# Serial-Basic-CH340E-and-USBC.net
KiCad netlist of a schematic drawn in EAGLE
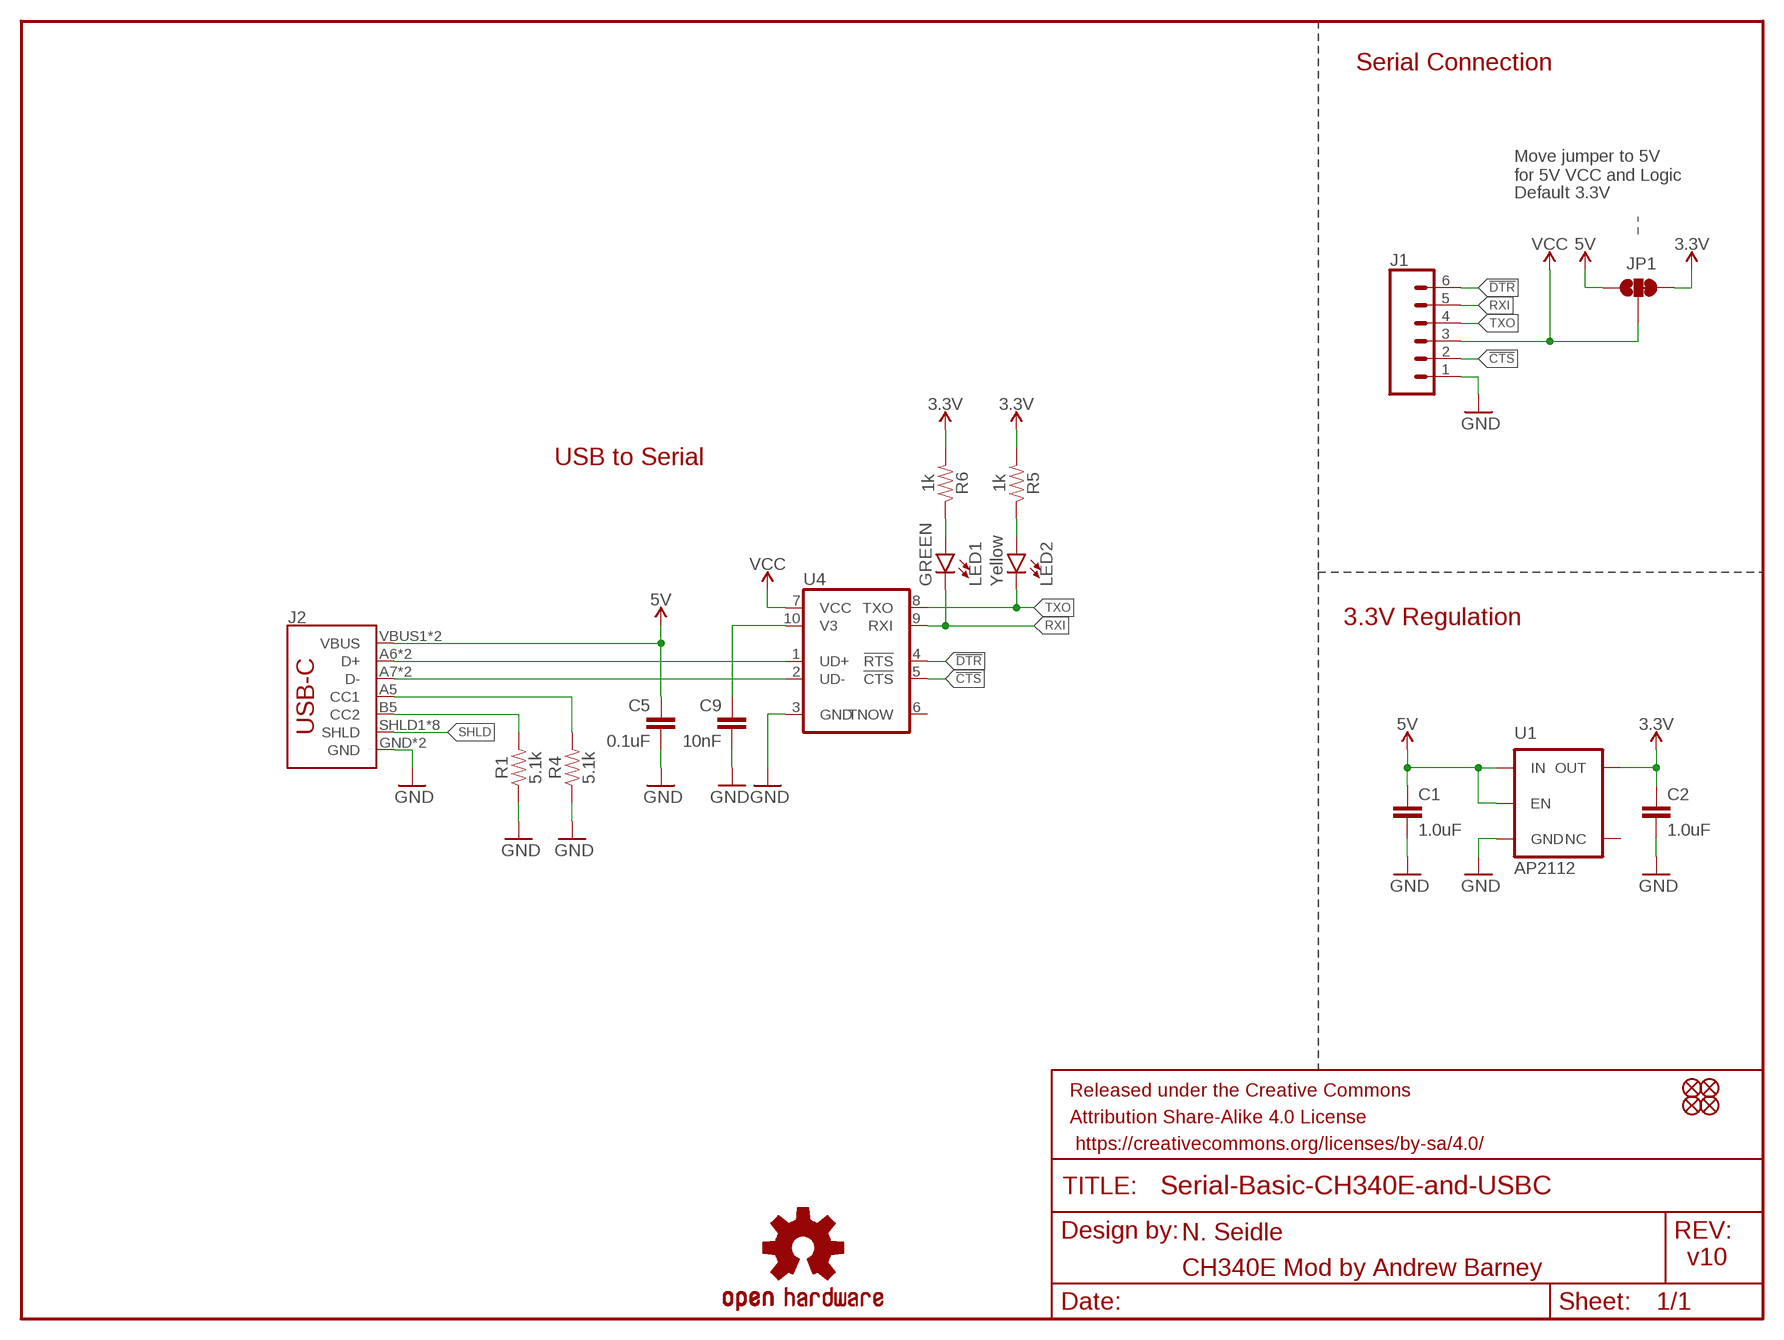
[diagram p0: schematic, sheet 1]

(export (version "E")
  (design (tool "Eeschema 10.0.6"))
  (components
    (comp (ref "C1")
      (value "1.0uF")
      (footprint "eagle-import:0603")
      (libsource (lib "eagle-import") (part "1.0UF-0603-16V-10%"))
    )
    (comp (ref "C2")
      (value "1.0uF")
      (footprint "eagle-import:0603")
      (libsource (lib "eagle-import") (part "1.0UF-0603-16V-10%"))
    )
    (comp (ref "C5")
      (value "0.1uF")
      (footprint "eagle-import:0603")
      (libsource (lib "eagle-import") (part "0.1UF-0603-25V-(+80/-20%)"))
    )
    (comp (ref "C9")
      (value "10nF")
      (footprint "eagle-import:0603")
      (libsource (lib "eagle-import") (part "10NF-0603-50V-10%"))
    )
    (comp (ref "FRAME1")
      (value "FRAME-LETTER")
      (footprint "eagle-import:CREATIVE_COMMONS")
      (libsource (lib "eagle-import") (part "FRAME-LETTER"))
    )
    (comp (ref "J1")
      (value "CONN_06SMD-FEMALE-V2")
      (footprint "eagle-import:1X06-SMD-FEMALE")
      (libsource (lib "eagle-import") (part "CONN_06SMD-FEMALE-V2"))
    )
    (comp (ref "J2")
      (value "USB_C16PIN")
      (footprint "eagle-import:USB-C-16P")
      (libsource (lib "eagle-import") (part "USB_C16PIN"))
    )
    (comp (ref "JP1")
      (value "JUMPER-SMT_3_1-NC_TRACE_SILK")
      (footprint "eagle-import:SMT-JUMPER_3_1-NC_TRACE_SILK")
      (libsource (lib "eagle-import") (part "JUMPER-SMT_3_1-NC_TRACE_SILK"))
    )
    (comp (ref "JP3")
      (value "FIDUCIAL1X2")
      (footprint "eagle-import:FIDUCIAL-1X2")
      (libsource (lib "eagle-import") (part "FIDUCIAL1X2"))
    )
    (comp (ref "JP4")
      (value "FIDUCIAL1X2")
      (footprint "eagle-import:FIDUCIAL-1X2")
      (libsource (lib "eagle-import") (part "FIDUCIAL1X2"))
    )
    (comp (ref "JP5")
      (value "FIDUCIAL1X2")
      (footprint "eagle-import:FIDUCIAL-1X2")
      (libsource (lib "eagle-import") (part "FIDUCIAL1X2"))
    )
    (comp (ref "JP6")
      (value "FIDUCIAL1X2")
      (footprint "eagle-import:FIDUCIAL-1X2")
      (libsource (lib "eagle-import") (part "FIDUCIAL1X2"))
    )
    (comp (ref "LED1")
      (value "GREEN")
      (footprint "eagle-import:LED-0603")
      (libsource (lib "eagle-import") (part "LED-GREEN0603"))
    )
    (comp (ref "LED2")
      (value "Yellow")
      (footprint "eagle-import:LED-0603")
      (libsource (lib "eagle-import") (part "LED-YELLOW0603"))
    )
    (comp (ref "LOGO1")
      (value "OSHW-LOGOS")
      (footprint "eagle-import:OSHW-LOGO-S")
      (libsource (lib "eagle-import") (part "OSHW-LOGOS"))
    )
    (comp (ref "R1")
      (value "5.1k")
      (footprint "eagle-import:0603")
      (libsource (lib "eagle-import") (part "5.1KOHM5.1KOHM-0603-1/10W-1%"))
    )
    (comp (ref "R4")
      (value "5.1k")
      (footprint "eagle-import:0603")
      (libsource (lib "eagle-import") (part "5.1KOHM5.1KOHM-0603-1/10W-1%"))
    )
    (comp (ref "R5")
      (value "1k")
      (footprint "eagle-import:0603")
      (libsource (lib "eagle-import") (part "1KOHM-0603-1/10W-1%"))
    )
    (comp (ref "R6")
      (value "1k")
      (footprint "eagle-import:0603")
      (libsource (lib "eagle-import") (part "1KOHM-0603-1/10W-1%"))
    )
    (comp (ref "U1")
      (value "3.3V")
      (footprint "eagle-import:SOT23-5")
      (libsource (lib "eagle-import") (part "V_REG_AP2112K-3.3V"))
    )
    (comp (ref "U4")
      (value "CH340E_MSOP10")
      (footprint "eagle-import:MSOP10")
      (libsource (lib "eagle-import") (part "CH340E_MSOP10"))
    )
  )
  (nets
    (net (code "1") (name "/~{CTS}") (class "Default")
      (node (ref "J1") (pin "2") (pinfunction "2_2") (pintype "passive"))
      (node (ref "U4") (pin "5") (pinfunction "~{CTS}_5") (pintype "bidirectional"))
    )
    (net (code "2") (name "/~{DTR}") (class "Default")
      (node (ref "J1") (pin "6") (pinfunction "6_6") (pintype "passive"))
      (node (ref "U4") (pin "4") (pinfunction "~{RTS}_4") (pintype "bidirectional"))
    )
    (net (code "3") (name "3.3V") (class "Default")
      (node (ref "C2") (pin "1") (pinfunction "1_1") (pintype "passive"))
      (node (ref "JP1") (pin "3") (pinfunction "3_3") (pintype "passive"))
      (node (ref "R5") (pin "2") (pinfunction "2_2") (pintype "passive"))
      (node (ref "R6") (pin "2") (pinfunction "2_2") (pintype "passive"))
      (node (ref "U1") (pin "5") (pinfunction "OUT_5") (pintype "passive"))
    )
    (net (code "4") (name "5V") (class "Default")
      (node (ref "C1") (pin "1") (pinfunction "1_1") (pintype "passive"))
      (node (ref "C5") (pin "1") (pinfunction "1_1") (pintype "passive"))
      (node (ref "J2") (pin "VBUS1") (pinfunction "VBUS_VBUS1") (pintype "bidirectional"))
      (node (ref "J2") (pin "VBUS2") (pinfunction "VBUS_VBUS2") (pintype "bidirectional"))
      (node (ref "JP1") (pin "1") (pinfunction "1_1") (pintype "passive"))
      (node (ref "U1") (pin "1") (pinfunction "IN_1") (pintype "input"))
      (node (ref "U1") (pin "3") (pinfunction "EN_3") (pintype "input"))
    )
    (net (code "5") (name "GND") (class "Default")
      (node (ref "C1") (pin "2") (pinfunction "2_2") (pintype "passive"))
      (node (ref "C2") (pin "2") (pinfunction "2_2") (pintype "passive"))
      (node (ref "C5") (pin "2") (pinfunction "2_2") (pintype "passive"))
      (node (ref "C9") (pin "2") (pinfunction "2_2") (pintype "passive"))
      (node (ref "J1") (pin "1") (pinfunction "1_1") (pintype "passive"))
      (node (ref "J2") (pin "GND") (pinfunction "GND_GND") (pintype "bidirectional"))
      (node (ref "J2") (pin "GND2") (pinfunction "GND_GND2") (pintype "bidirectional"))
      (node (ref "R1") (pin "1") (pinfunction "1_1") (pintype "passive"))
      (node (ref "R4") (pin "1") (pinfunction "1_1") (pintype "passive"))
      (node (ref "U1") (pin "2") (pinfunction "GND_2") (pintype "input"))
      (node (ref "U4") (pin "3") (pinfunction "GND_3") (pintype "bidirectional"))
    )
    (net (code "6") (name "Net-(J2-CC1)") (class "Default")
      (node (ref "J2") (pin "A5") (pinfunction "CC1_A5") (pintype "bidirectional"))
      (node (ref "R4") (pin "2") (pinfunction "2_2") (pintype "passive"))
    )
    (net (code "7") (name "Net-(J2-CC2)") (class "Default")
      (node (ref "J2") (pin "B5") (pinfunction "CC2_B5") (pintype "bidirectional"))
      (node (ref "R1") (pin "2") (pinfunction "2_2") (pintype "passive"))
    )
    (net (code "8") (name "Net-(LED1-PadA)") (class "Default")
      (node (ref "LED1") (pin "A") (pinfunction "A_A") (pintype "passive"))
      (node (ref "R6") (pin "1") (pinfunction "1_1") (pintype "passive"))
    )
    (net (code "9") (name "Net-(LED2-PadA)") (class "Default")
      (node (ref "LED2") (pin "A") (pinfunction "A_A") (pintype "passive"))
      (node (ref "R5") (pin "1") (pinfunction "1_1") (pintype "passive"))
    )
    (net (code "10") (name "Net-(U4-UD+)") (class "Default")
      (node (ref "J2") (pin "A6") (pinfunction "D+_A6") (pintype "bidirectional"))
      (node (ref "J2") (pin "B6") (pinfunction "D+_B6") (pintype "bidirectional"))
      (node (ref "U4") (pin "1") (pinfunction "UD+_1") (pintype "bidirectional"))
    )
    (net (code "11") (name "Net-(U4-UD-)") (class "Default")
      (node (ref "J2") (pin "A7") (pinfunction "D-_A7") (pintype "bidirectional"))
      (node (ref "J2") (pin "B7") (pinfunction "D-_B7") (pintype "bidirectional"))
      (node (ref "U4") (pin "2") (pinfunction "UD-_2") (pintype "bidirectional"))
    )
    (net (code "12") (name "Net-(U4-V3)") (class "Default")
      (node (ref "C9") (pin "1") (pinfunction "1_1") (pintype "passive"))
      (node (ref "U4") (pin "10") (pinfunction "V3_10") (pintype "bidirectional"))
    )
    (net (code "13") (name "RXI") (class "Default")
      (node (ref "J1") (pin "5") (pinfunction "5_5") (pintype "passive"))
      (node (ref "LED1") (pin "C") (pinfunction "C_C") (pintype "passive"))
      (node (ref "U4") (pin "9") (pinfunction "RXI_9") (pintype "bidirectional"))
    )
    (net (code "14") (name "SHLD") (class "Default")
      (node (ref "J2") (pin "SHLD1") (pinfunction "SHLD_SHLD1") (pintype "bidirectional"))
      (node (ref "J2") (pin "SHLD2") (pinfunction "SHLD_SHLD2") (pintype "bidirectional"))
      (node (ref "J2") (pin "SHLD3") (pinfunction "SHLD_SHLD3") (pintype "bidirectional"))
      (node (ref "J2") (pin "SHLD4") (pinfunction "SHLD_SHLD4") (pintype "bidirectional"))
      (node (ref "J2") (pin "SHLD5") (pinfunction "SHLD_SHLD5") (pintype "bidirectional"))
      (node (ref "J2") (pin "SHLD6") (pinfunction "SHLD_SHLD6") (pintype "bidirectional"))
      (node (ref "J2") (pin "SHLD7") (pinfunction "SHLD_SHLD7") (pintype "bidirectional"))
      (node (ref "J2") (pin "SHLD8") (pinfunction "SHLD_SHLD8") (pintype "bidirectional"))
    )
    (net (code "15") (name "TXO") (class "Default")
      (node (ref "J1") (pin "4") (pinfunction "4_4") (pintype "passive"))
      (node (ref "LED2") (pin "C") (pinfunction "C_C") (pintype "passive"))
      (node (ref "U4") (pin "8") (pinfunction "TXO_8") (pintype "bidirectional"))
    )
    (net (code "16") (name "VCC") (class "Default")
      (node (ref "J1") (pin "3") (pinfunction "3_3") (pintype "passive"))
      (node (ref "JP1") (pin "2") (pinfunction "2_2") (pintype "passive"))
      (node (ref "U4") (pin "7") (pinfunction "VCC_7") (pintype "bidirectional"))
    )
    (net (code "17") (name "unconnected-(U1-NC-Pad4)") (class "Default")
      (node (ref "U1") (pin "4") (pinfunction "NC_4") (pintype "no_connect"))
    )
    (net (code "18") (name "unconnected-(U4-TNOW-Pad6)") (class "Default")
      (node (ref "U4") (pin "6") (pinfunction "TNOW_6") (pintype "bidirectional"))
    )
  )
)
